# ProPrj_hackpod.net
KiCad netlist of a schematic drawn in EasyEDA Pro
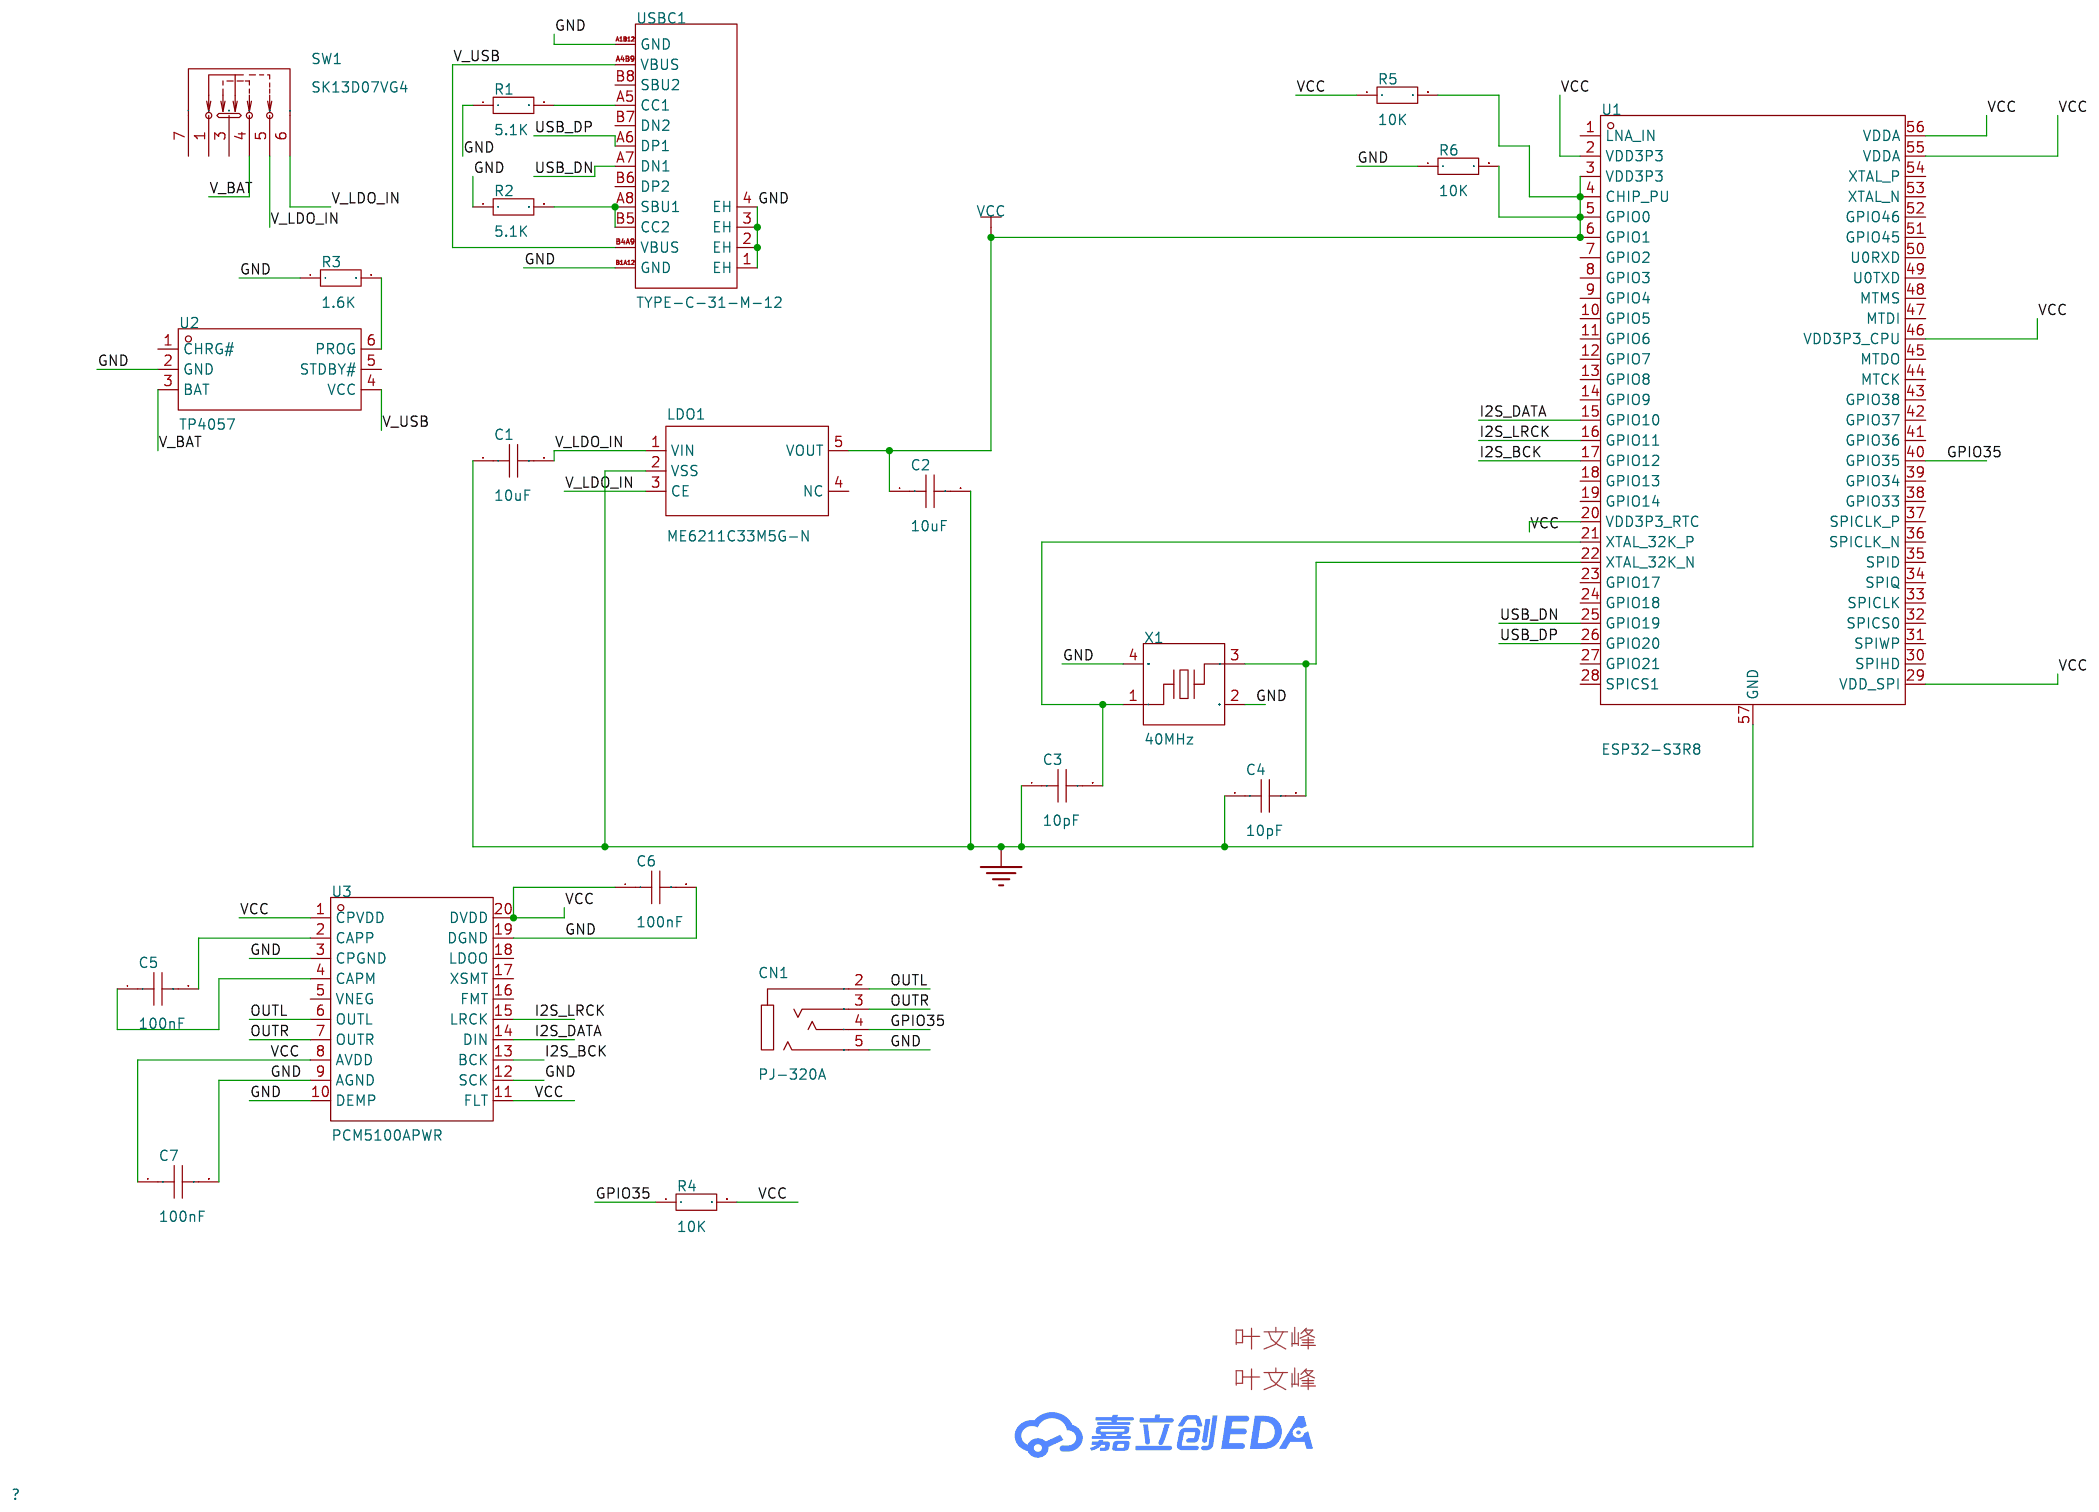
[diagram p0: schematic sheet]

(export (version "E")
  (design (tool "Eeschema 10.0.6"))
  (components
    (comp (ref "C1")
      (value "10uF")
      (footprint "easyedapro:C0603")
      (libsource (lib "easyedapro") (part "Capacitance"))
    )
    (comp (ref "C2")
      (value "10uF")
      (footprint "easyedapro:C0603")
      (libsource (lib "easyedapro") (part "Capacitance"))
    )
    (comp (ref "C3")
      (value "10pF")
      (footprint "easyedapro:C0603")
      (libsource (lib "easyedapro") (part "Capacitance"))
    )
    (comp (ref "C4")
      (value "10pF")
      (footprint "easyedapro:C0603")
      (libsource (lib "easyedapro") (part "Capacitance"))
    )
    (comp (ref "C5")
      (value "100nF")
      (footprint "easyedapro:C0603")
      (libsource (lib "easyedapro") (part "Capacitance"))
    )
    (comp (ref "C6")
      (value "100nF")
      (footprint "easyedapro:C0603")
      (libsource (lib "easyedapro") (part "Capacitance"))
    )
    (comp (ref "C7")
      (value "100nF")
      (footprint "easyedapro:C0603")
      (libsource (lib "easyedapro") (part "Capacitance"))
    )
    (comp (ref "CN1")
      (value "PJ-320A")
      (footprint "easyedapro:AUDIO-TH_PJ-320A_C49284721")
      (description "连接器类型:3.5mm耳机座;额定电流:500mA;额定电压:30V;触头材质:铜;触头镀层:金;工作温度:-25°C~+85°C;")
      (fields (field (name "Manufacturer") "XUNPU(讯普)"))
      (libsource (lib "easyedapro") (part "PJ-320A_C49284721"))
    )
    (comp (ref "LDO1")
      (value "ME6211C33M5G-N")
      (footprint "easyedapro:SOT-23-5_L3.0-W1.7-P0.95-LS2.8-BL")
      (description "输出类型:固定;工作电压:6V;输出电压:3.3V;输出电流:500mA;电源纹波抑制比(PSRR):70dB@(1kHz);输出极性:正极;")
      (fields (field (name "Manufacturer") "MICRONE(南京微盟)"))
      (libsource (lib "easyedapro") (part "ME6211C33M5G-N"))
    )
    (comp (ref "R1") (value "5.1K") (footprint "easyedapro:R0603") (libsource (lib "easyedapro") (part "电阻")))
    (comp (ref "R2") (value "5.1K") (footprint "easyedapro:R0603") (libsource (lib "easyedapro") (part "电阻")))
    (comp (ref "R3") (value "1.6K") (footprint "easyedapro:R0603") (libsource (lib "easyedapro") (part "电阻")))
    (comp (ref "R4") (value "10K") (footprint "easyedapro:R0603") (libsource (lib "easyedapro") (part "电阻")))
    (comp (ref "R5") (value "10K") (footprint "easyedapro:R0603") (libsource (lib "easyedapro") (part "电阻")))
    (comp (ref "R6") (value "10K") (footprint "easyedapro:R0603") (libsource (lib "easyedapro") (part "电阻")))
    (comp (ref "SW1")
      (value "SK13D07VG4")
      (footprint "easyedapro:SW-TH_SK13D07VG4")
      (description "电路结构:单刀三掷;安装方式:-;开关颜色:-;额定电流:300mA;额定电压:50V;工作寿命:5千次;")
      (fields (field (name "Manufacturer") "SHOU HAN(首韩)"))
      (libsource (lib "easyedapro") (part "SK13D07VG4"))
    )
    (comp (ref "U1")
      (value "ESP32-S3R8")
      (footprint "easyedapro:QFN-56_L7.0-W7.0-P0.40-TL-EP4.0")
      (fields (field (name "Manufacturer") "ESPRESSIF(乐鑫)"))
      (libsource (lib "easyedapro") (part "ESP32-S3(R8)"))
    )
    (comp (ref "U2")
      (value "TP4057")
      (footprint "easyedapro:SOT-23-6_L2.9-W1.6-P0.95-LS2.8-BR")
      (description "工作电压:4V~6.5V;最大充电电流:500mA;电池类型:锂离子;电池节数:1;")
      (fields (field (name "Manufacturer") "UMW(友台半导体)"))
      (libsource (lib "easyedapro") (part "TP4057_C725791"))
    )
    (comp (ref "U3")
      (value "PCM5100APWR")
      (footprint "easyedapro:TSSOP-20_L6.5-W4.4-P0.65-LS6.4-BL")
      (description "工作电压:1.8V~3.3V;接口类型:I2S;")
      (fields (field (name "Manufacturer") "TI(德州仪器)"))
      (libsource (lib "easyedapro") (part "PCM5100APWR"))
    )
    (comp (ref "USBC1")
      (value "TYPE-C-31-M-12")
      (footprint "easyedapro:USB-C_SMD-TYPE-C-31-M-12_1")
      (description "连接器类型:Type-C;协议标准:-;公母:母;安装方式:-;触点数量:16P;端口数量:1;额定电流 - 电源:5A;工作温度:-;")
      (fields (field (name "Manufacturer") "韩国韩荣"))
      (libsource (lib "easyedapro") (part "TYPE-C-31-M-12"))
    )
    (comp (ref "X1")
      (value "40MHz")
      (footprint "easyedapro:CRYSTAL-SMD_4P-L3.2-W2.5-BL")
      (description "晶振类型:贴片晶振;频率:40MHz;常温频差:±10ppm;负载电容:15pF;频率稳定度:±20ppm;")
      (fields
        (field (name "Manufacturer Part") "XL2EL89CPI-111YLC-40M")
        (field (name "Manufacturer") "YXC(扬兴晶振)")
      )
      (libsource (lib "easyedapro") (part "XL2EL89CPI-111YLC-40M"))
    )
  )
  (nets
    (net (code "1") (name "/GPIO35") (class "Default")
      (node (ref "CN1") (pin "4") (pinfunction "4_4") (pintype "unspecified"))
      (node (ref "R4") (pin "1") (pinfunction "1_1") (pintype "input"))
      (node (ref "U1") (pin "40") (pinfunction "GPIO35_40") (pintype "unspecified"))
    )
    (net (code "2") (name "/I2S_BCK") (class "Default")
      (node (ref "U1") (pin "17") (pinfunction "GPIO12_17") (pintype "unspecified"))
      (node (ref "U3") (pin "13") (pinfunction "BCK_13") (pintype "unspecified"))
    )
    (net (code "3") (name "/I2S_DATA") (class "Default")
      (node (ref "U1") (pin "15") (pinfunction "GPIO10_15") (pintype "unspecified"))
      (node (ref "U3") (pin "14") (pinfunction "DIN_14") (pintype "unspecified"))
    )
    (net (code "4") (name "/I2S_LRCK") (class "Default")
      (node (ref "U1") (pin "16") (pinfunction "GPIO11_16") (pintype "unspecified"))
      (node (ref "U3") (pin "15") (pinfunction "LRCK_15") (pintype "unspecified"))
    )
    (net (code "5") (name "/OUTL") (class "Default")
      (node (ref "CN1") (pin "2") (pinfunction "2_2") (pintype "unspecified"))
      (node (ref "U3") (pin "6") (pinfunction "OUTL_6") (pintype "unspecified"))
    )
    (net (code "6") (name "/OUTR") (class "Default")
      (node (ref "CN1") (pin "3") (pinfunction "3_3") (pintype "unspecified"))
      (node (ref "U3") (pin "7") (pinfunction "OUTR_7") (pintype "unspecified"))
    )
    (net (code "7") (name "/USB_DN") (class "Default")
      (node (ref "U1") (pin "25") (pinfunction "GPIO19_25") (pintype "unspecified"))
      (node (ref "USBC1") (pin "A7") (pinfunction "DN1_A7") (pintype "unspecified"))
    )
    (net (code "8") (name "/USB_DP") (class "Default")
      (node (ref "U1") (pin "26") (pinfunction "GPIO20_26") (pintype "unspecified"))
      (node (ref "USBC1") (pin "A6") (pinfunction "DP1_A6") (pintype "unspecified"))
    )
    (net (code "9") (name "/V_BAT") (class "Default")
      (node (ref "SW1") (pin "4") (pinfunction "4_4") (pintype "unspecified"))
      (node (ref "U2") (pin "3") (pinfunction "BAT_3") (pintype "unspecified"))
    )
    (net (code "10") (name "/V_LDO_IN") (class "Default")
      (node (ref "C1") (pin "2") (pinfunction "2_2") (pintype "input"))
      (node (ref "LDO1") (pin "1") (pinfunction "VIN_1") (pintype "unspecified"))
      (node (ref "LDO1") (pin "3") (pinfunction "CE_3") (pintype "unspecified"))
      (node (ref "SW1") (pin "5") (pinfunction "5_5") (pintype "unspecified"))
      (node (ref "SW1") (pin "6") (pinfunction "6_6") (pintype "unspecified"))
    )
    (net (code "11") (name "/V_USB") (class "Default")
      (node (ref "U2") (pin "4") (pinfunction "VCC_4") (pintype "unspecified"))
      (node (ref "USBC1") (pin "A4B9") (pinfunction "VBUS_A4B9") (pintype "unspecified"))
      (node (ref "USBC1") (pin "B4A9") (pinfunction "VBUS_B4A9") (pintype "unspecified"))
    )
    (net (code "12") (name "GND") (class "Default")
      (node (ref "C1") (pin "1") (pinfunction "1_1") (pintype "input"))
      (node (ref "C2") (pin "2") (pinfunction "2_2") (pintype "input"))
      (node (ref "C3") (pin "1") (pinfunction "1_1") (pintype "input"))
      (node (ref "C4") (pin "1") (pinfunction "1_1") (pintype "input"))
      (node (ref "C6") (pin "2") (pinfunction "2_2") (pintype "input"))
      (node (ref "C7") (pin "2") (pinfunction "2_2") (pintype "input"))
      (node (ref "CN1") (pin "5") (pinfunction "5_5") (pintype "unspecified"))
      (node (ref "LDO1") (pin "2") (pinfunction "VSS_2") (pintype "unspecified"))
      (node (ref "R1") (pin "1") (pinfunction "1_1") (pintype "input"))
      (node (ref "R2") (pin "1") (pinfunction "1_1") (pintype "input"))
      (node (ref "R3") (pin "1") (pinfunction "1_1") (pintype "input"))
      (node (ref "R6") (pin "1") (pinfunction "1_1") (pintype "input"))
      (node (ref "U1") (pin "57") (pinfunction "GND_57") (pintype "unspecified"))
      (node (ref "U2") (pin "2") (pinfunction "GND_2") (pintype "unspecified"))
      (node (ref "U3") (pin "10") (pinfunction "DEMP_10") (pintype "unspecified"))
      (node (ref "U3") (pin "12") (pinfunction "SCK_12") (pintype "unspecified"))
      (node (ref "U3") (pin "19") (pinfunction "DGND_19") (pintype "unspecified"))
      (node (ref "U3") (pin "3") (pinfunction "CPGND_3") (pintype "unspecified"))
      (node (ref "U3") (pin "9") (pinfunction "AGND_9") (pintype "unspecified"))
      (node (ref "USBC1") (pin "1") (pinfunction "EH_1") (pintype "unspecified"))
      (node (ref "USBC1") (pin "2") (pinfunction "EH_2") (pintype "unspecified"))
      (node (ref "USBC1") (pin "3") (pinfunction "EH_3") (pintype "unspecified"))
      (node (ref "USBC1") (pin "4") (pinfunction "EH_4") (pintype "unspecified"))
      (node (ref "USBC1") (pin "A1B12") (pinfunction "GND_A1B12") (pintype "unspecified"))
      (node (ref "USBC1") (pin "B1A12") (pinfunction "GND_B1A12") (pintype "unspecified"))
      (node (ref "X1") (pin "2") (pinfunction "GND_2") (pintype "input"))
      (node (ref "X1") (pin "4") (pinfunction "GND_4") (pintype "input"))
    )
    (net (code "13") (name "Net-(U1-XTAL_32K_N)") (class "Default")
      (node (ref "C4") (pin "2") (pinfunction "2_2") (pintype "input"))
      (node (ref "U1") (pin "22") (pinfunction "XTAL_32K_N_22") (pintype "unspecified"))
      (node (ref "X1") (pin "3") (pinfunction "3_3") (pintype "input"))
    )
    (net (code "14") (name "Net-(U1-XTAL_32K_P)") (class "Default")
      (node (ref "C3") (pin "2") (pinfunction "2_2") (pintype "input"))
      (node (ref "U1") (pin "21") (pinfunction "XTAL_32K_P_21") (pintype "unspecified"))
      (node (ref "X1") (pin "1") (pinfunction "1_1") (pintype "input"))
    )
    (net (code "15") (name "Net-(U2-PROG)") (class "Default")
      (node (ref "R3") (pin "2") (pinfunction "2_2") (pintype "input"))
      (node (ref "U2") (pin "6") (pinfunction "PROG_6") (pintype "unspecified"))
    )
    (net (code "16") (name "Net-(U3-CAPM)") (class "Default")
      (node (ref "C5") (pin "1") (pinfunction "1_1") (pintype "input"))
      (node (ref "U3") (pin "4") (pinfunction "CAPM_4") (pintype "unspecified"))
    )
    (net (code "17") (name "Net-(U3-CAPP)") (class "Default")
      (node (ref "C5") (pin "2") (pinfunction "2_2") (pintype "input"))
      (node (ref "U3") (pin "2") (pinfunction "CAPP_2") (pintype "unspecified"))
    )
    (net (code "18") (name "Net-(USBC1-CC1)") (class "Default")
      (node (ref "R1") (pin "2") (pinfunction "2_2") (pintype "input"))
      (node (ref "USBC1") (pin "A5") (pinfunction "CC1_A5") (pintype "unspecified"))
    )
    (net (code "19") (name "Net-(USBC1-CC2)") (class "Default")
      (node (ref "R2") (pin "2") (pinfunction "2_2") (pintype "input"))
      (node (ref "USBC1") (pin "A8") (pinfunction "SBU1_A8") (pintype "unspecified"))
      (node (ref "USBC1") (pin "B5") (pinfunction "CC2_B5") (pintype "unspecified"))
    )
    (net (code "20") (name "VCC") (class "Default")
      (node (ref "C2") (pin "1") (pinfunction "1_1") (pintype "input"))
      (node (ref "C6") (pin "1") (pinfunction "1_1") (pintype "input"))
      (node (ref "C7") (pin "1") (pinfunction "1_1") (pintype "input"))
      (node (ref "LDO1") (pin "5") (pinfunction "VOUT_5") (pintype "unspecified"))
      (node (ref "R4") (pin "2") (pinfunction "2_2") (pintype "input"))
      (node (ref "R5") (pin "1") (pinfunction "1_1") (pintype "input"))
      (node (ref "R5") (pin "2") (pinfunction "2_2") (pintype "input"))
      (node (ref "R6") (pin "2") (pinfunction "2_2") (pintype "input"))
      (node (ref "U1") (pin "2") (pinfunction "VDD3P3_2") (pintype "unspecified"))
      (node (ref "U1") (pin "20") (pinfunction "VDD3P3_RTC_20") (pintype "unspecified"))
      (node (ref "U1") (pin "29") (pinfunction "VDD_SPI_29") (pintype "unspecified"))
      (node (ref "U1") (pin "3") (pinfunction "VDD3P3_3") (pintype "unspecified"))
      (node (ref "U1") (pin "4") (pinfunction "CHIP_PU_4") (pintype "unspecified"))
      (node (ref "U1") (pin "46") (pinfunction "VDD3P3_CPU_46") (pintype "unspecified"))
      (node (ref "U1") (pin "5") (pinfunction "GPIO0_5") (pintype "unspecified"))
      (node (ref "U1") (pin "55") (pinfunction "VDDA_55") (pintype "unspecified"))
      (node (ref "U1") (pin "56") (pinfunction "VDDA_56") (pintype "unspecified"))
      (node (ref "U1") (pin "6") (pinfunction "GPIO1_6") (pintype "unspecified"))
      (node (ref "U3") (pin "1") (pinfunction "CPVDD_1") (pintype "unspecified"))
      (node (ref "U3") (pin "11") (pinfunction "FLT_11") (pintype "unspecified"))
      (node (ref "U3") (pin "20") (pinfunction "DVDD_20") (pintype "unspecified"))
      (node (ref "U3") (pin "8") (pinfunction "AVDD_8") (pintype "unspecified"))
    )
    (net (code "21") (name "unconnected-(LDO1-NC-Pad4)") (class "Default")
      (node (ref "LDO1") (pin "4") (pinfunction "NC_4") (pintype "unspecified"))
    )
    (net (code "22") (name "unconnected-(SW1-Pad1)") (class "Default")
      (node (ref "SW1") (pin "1") (pinfunction "1_1") (pintype "unspecified"))
    )
    (net (code "23") (name "unconnected-(SW1-Pad3)") (class "Default")
      (node (ref "SW1") (pin "3") (pinfunction "3_3") (pintype "unspecified"))
    )
    (net (code "24") (name "unconnected-(SW1-Pad7)") (class "Default")
      (node (ref "SW1") (pin "7") (pinfunction "7_7") (pintype "unspecified"))
    )
    (net (code "25") (name "unconnected-(U1-GPIO2-Pad7)") (class "Default")
      (node (ref "U1") (pin "7") (pinfunction "GPIO2_7") (pintype "unspecified"))
    )
    (net (code "26") (name "unconnected-(U1-GPIO3-Pad8)") (class "Default")
      (node (ref "U1") (pin "8") (pinfunction "GPIO3_8") (pintype "unspecified"))
    )
    (net (code "27") (name "unconnected-(U1-GPIO4-Pad9)") (class "Default")
      (node (ref "U1") (pin "9") (pinfunction "GPIO4_9") (pintype "unspecified"))
    )
    (net (code "28") (name "unconnected-(U1-GPIO5-Pad10)") (class "Default")
      (node (ref "U1") (pin "10") (pinfunction "GPIO5_10") (pintype "unspecified"))
    )
    (net (code "29") (name "unconnected-(U1-GPIO6-Pad11)") (class "Default")
      (node (ref "U1") (pin "11") (pinfunction "GPIO6_11") (pintype "unspecified"))
    )
    (net (code "30") (name "unconnected-(U1-GPIO7-Pad12)") (class "Default")
      (node (ref "U1") (pin "12") (pinfunction "GPIO7_12") (pintype "unspecified"))
    )
    (net (code "31") (name "unconnected-(U1-GPIO8-Pad13)") (class "Default")
      (node (ref "U1") (pin "13") (pinfunction "GPIO8_13") (pintype "unspecified"))
    )
    (net (code "32") (name "unconnected-(U1-GPIO9-Pad14)") (class "Default")
      (node (ref "U1") (pin "14") (pinfunction "GPIO9_14") (pintype "unspecified"))
    )
    (net (code "33") (name "unconnected-(U1-GPIO13-Pad18)") (class "Default")
      (node (ref "U1") (pin "18") (pinfunction "GPIO13_18") (pintype "unspecified"))
    )
    (net (code "34") (name "unconnected-(U1-GPIO14-Pad19)") (class "Default")
      (node (ref "U1") (pin "19") (pinfunction "GPIO14_19") (pintype "unspecified"))
    )
    (net (code "35") (name "unconnected-(U1-GPIO17-Pad23)") (class "Default")
      (node (ref "U1") (pin "23") (pinfunction "GPIO17_23") (pintype "unspecified"))
    )
    (net (code "36") (name "unconnected-(U1-GPIO18-Pad24)") (class "Default")
      (node (ref "U1") (pin "24") (pinfunction "GPIO18_24") (pintype "unspecified"))
    )
    (net (code "37") (name "unconnected-(U1-GPIO21-Pad27)") (class "Default")
      (node (ref "U1") (pin "27") (pinfunction "GPIO21_27") (pintype "unspecified"))
    )
    (net (code "38") (name "unconnected-(U1-GPIO33-Pad38)") (class "Default")
      (node (ref "U1") (pin "38") (pinfunction "GPIO33_38") (pintype "unspecified"))
    )
    (net (code "39") (name "unconnected-(U1-GPIO34-Pad39)") (class "Default")
      (node (ref "U1") (pin "39") (pinfunction "GPIO34_39") (pintype "unspecified"))
    )
    (net (code "40") (name "unconnected-(U1-GPIO36-Pad41)") (class "Default")
      (node (ref "U1") (pin "41") (pinfunction "GPIO36_41") (pintype "unspecified"))
    )
    (net (code "41") (name "unconnected-(U1-GPIO37-Pad42)") (class "Default")
      (node (ref "U1") (pin "42") (pinfunction "GPIO37_42") (pintype "unspecified"))
    )
    (net (code "42") (name "unconnected-(U1-GPIO38-Pad43)") (class "Default")
      (node (ref "U1") (pin "43") (pinfunction "GPIO38_43") (pintype "unspecified"))
    )
    (net (code "43") (name "unconnected-(U1-GPIO45-Pad51)") (class "Default")
      (node (ref "U1") (pin "51") (pinfunction "GPIO45_51") (pintype "unspecified"))
    )
    (net (code "44") (name "unconnected-(U1-GPIO46-Pad52)") (class "Default")
      (node (ref "U1") (pin "52") (pinfunction "GPIO46_52") (pintype "unspecified"))
    )
    (net (code "45") (name "unconnected-(U1-LNA_IN-Pad1)") (class "Default")
      (node (ref "U1") (pin "1") (pinfunction "LNA_IN_1") (pintype "unspecified"))
    )
    (net (code "46") (name "unconnected-(U1-MTCK-Pad44)") (class "Default")
      (node (ref "U1") (pin "44") (pinfunction "MTCK_44") (pintype "unspecified"))
    )
    (net (code "47") (name "unconnected-(U1-MTDI-Pad47)") (class "Default")
      (node (ref "U1") (pin "47") (pinfunction "MTDI_47") (pintype "unspecified"))
    )
    (net (code "48") (name "unconnected-(U1-MTDO-Pad45)") (class "Default")
      (node (ref "U1") (pin "45") (pinfunction "MTDO_45") (pintype "unspecified"))
    )
    (net (code "49") (name "unconnected-(U1-MTMS-Pad48)") (class "Default")
      (node (ref "U1") (pin "48") (pinfunction "MTMS_48") (pintype "unspecified"))
    )
    (net (code "50") (name "unconnected-(U1-SPICLK-Pad33)") (class "Default")
      (node (ref "U1") (pin "33") (pinfunction "SPICLK_33") (pintype "unspecified"))
    )
    (net (code "51") (name "unconnected-(U1-SPICLK_N-Pad36)") (class "Default")
      (node (ref "U1") (pin "36") (pinfunction "SPICLK_N_36") (pintype "unspecified"))
    )
    (net (code "52") (name "unconnected-(U1-SPICLK_P-Pad37)") (class "Default")
      (node (ref "U1") (pin "37") (pinfunction "SPICLK_P_37") (pintype "unspecified"))
    )
    (net (code "53") (name "unconnected-(U1-SPICS0-Pad32)") (class "Default")
      (node (ref "U1") (pin "32") (pinfunction "SPICS0_32") (pintype "unspecified"))
    )
    (net (code "54") (name "unconnected-(U1-SPICS1-Pad28)") (class "Default")
      (node (ref "U1") (pin "28") (pinfunction "SPICS1_28") (pintype "unspecified"))
    )
    (net (code "55") (name "unconnected-(U1-SPID-Pad35)") (class "Default")
      (node (ref "U1") (pin "35") (pinfunction "SPID_35") (pintype "unspecified"))
    )
    (net (code "56") (name "unconnected-(U1-SPIHD-Pad30)") (class "Default")
      (node (ref "U1") (pin "30") (pinfunction "SPIHD_30") (pintype "unspecified"))
    )
    (net (code "57") (name "unconnected-(U1-SPIQ-Pad34)") (class "Default")
      (node (ref "U1") (pin "34") (pinfunction "SPIQ_34") (pintype "unspecified"))
    )
    (net (code "58") (name "unconnected-(U1-SPIWP-Pad31)") (class "Default")
      (node (ref "U1") (pin "31") (pinfunction "SPIWP_31") (pintype "unspecified"))
    )
    (net (code "59") (name "unconnected-(U1-U0RXD-Pad50)") (class "Default")
      (node (ref "U1") (pin "50") (pinfunction "U0RXD_50") (pintype "unspecified"))
    )
    (net (code "60") (name "unconnected-(U1-U0TXD-Pad49)") (class "Default")
      (node (ref "U1") (pin "49") (pinfunction "U0TXD_49") (pintype "unspecified"))
    )
    (net (code "61") (name "unconnected-(U1-XTAL_N-Pad53)") (class "Default")
      (node (ref "U1") (pin "53") (pinfunction "XTAL_N_53") (pintype "unspecified"))
    )
    (net (code "62") (name "unconnected-(U1-XTAL_P-Pad54)") (class "Default")
      (node (ref "U1") (pin "54") (pinfunction "XTAL_P_54") (pintype "unspecified"))
    )
    (net (code "63") (name "unconnected-(U2-CHRG#-Pad1)") (class "Default")
      (node (ref "U2") (pin "1") (pinfunction "CHRG#_1") (pintype "unspecified"))
    )
    (net (code "64") (name "unconnected-(U2-STDBY#-Pad5)") (class "Default")
      (node (ref "U2") (pin "5") (pinfunction "STDBY#_5") (pintype "unspecified"))
    )
    (net (code "65") (name "unconnected-(U3-FMT-Pad16)") (class "Default")
      (node (ref "U3") (pin "16") (pinfunction "FMT_16") (pintype "unspecified"))
    )
    (net (code "66") (name "unconnected-(U3-LDOO-Pad18)") (class "Default")
      (node (ref "U3") (pin "18") (pinfunction "LDOO_18") (pintype "unspecified"))
    )
    (net (code "67") (name "unconnected-(U3-VNEG-Pad5)") (class "Default")
      (node (ref "U3") (pin "5") (pinfunction "VNEG_5") (pintype "unspecified"))
    )
    (net (code "68") (name "unconnected-(U3-XSMT-Pad17)") (class "Default")
      (node (ref "U3") (pin "17") (pinfunction "XSMT_17") (pintype "unspecified"))
    )
    (net (code "69") (name "unconnected-(USBC1-DN2-PadB7)") (class "Default")
      (node (ref "USBC1") (pin "B7") (pinfunction "DN2_B7") (pintype "unspecified"))
    )
    (net (code "70") (name "unconnected-(USBC1-DP2-PadB6)") (class "Default")
      (node (ref "USBC1") (pin "B6") (pinfunction "DP2_B6") (pintype "unspecified"))
    )
    (net (code "71") (name "unconnected-(USBC1-SBU2-PadB8)") (class "Default")
      (node (ref "USBC1") (pin "B8") (pinfunction "SBU2_B8") (pintype "unspecified"))
    )
  )
)
